# p02.net
KiCad netlist of a schematic drawn in EAGLE
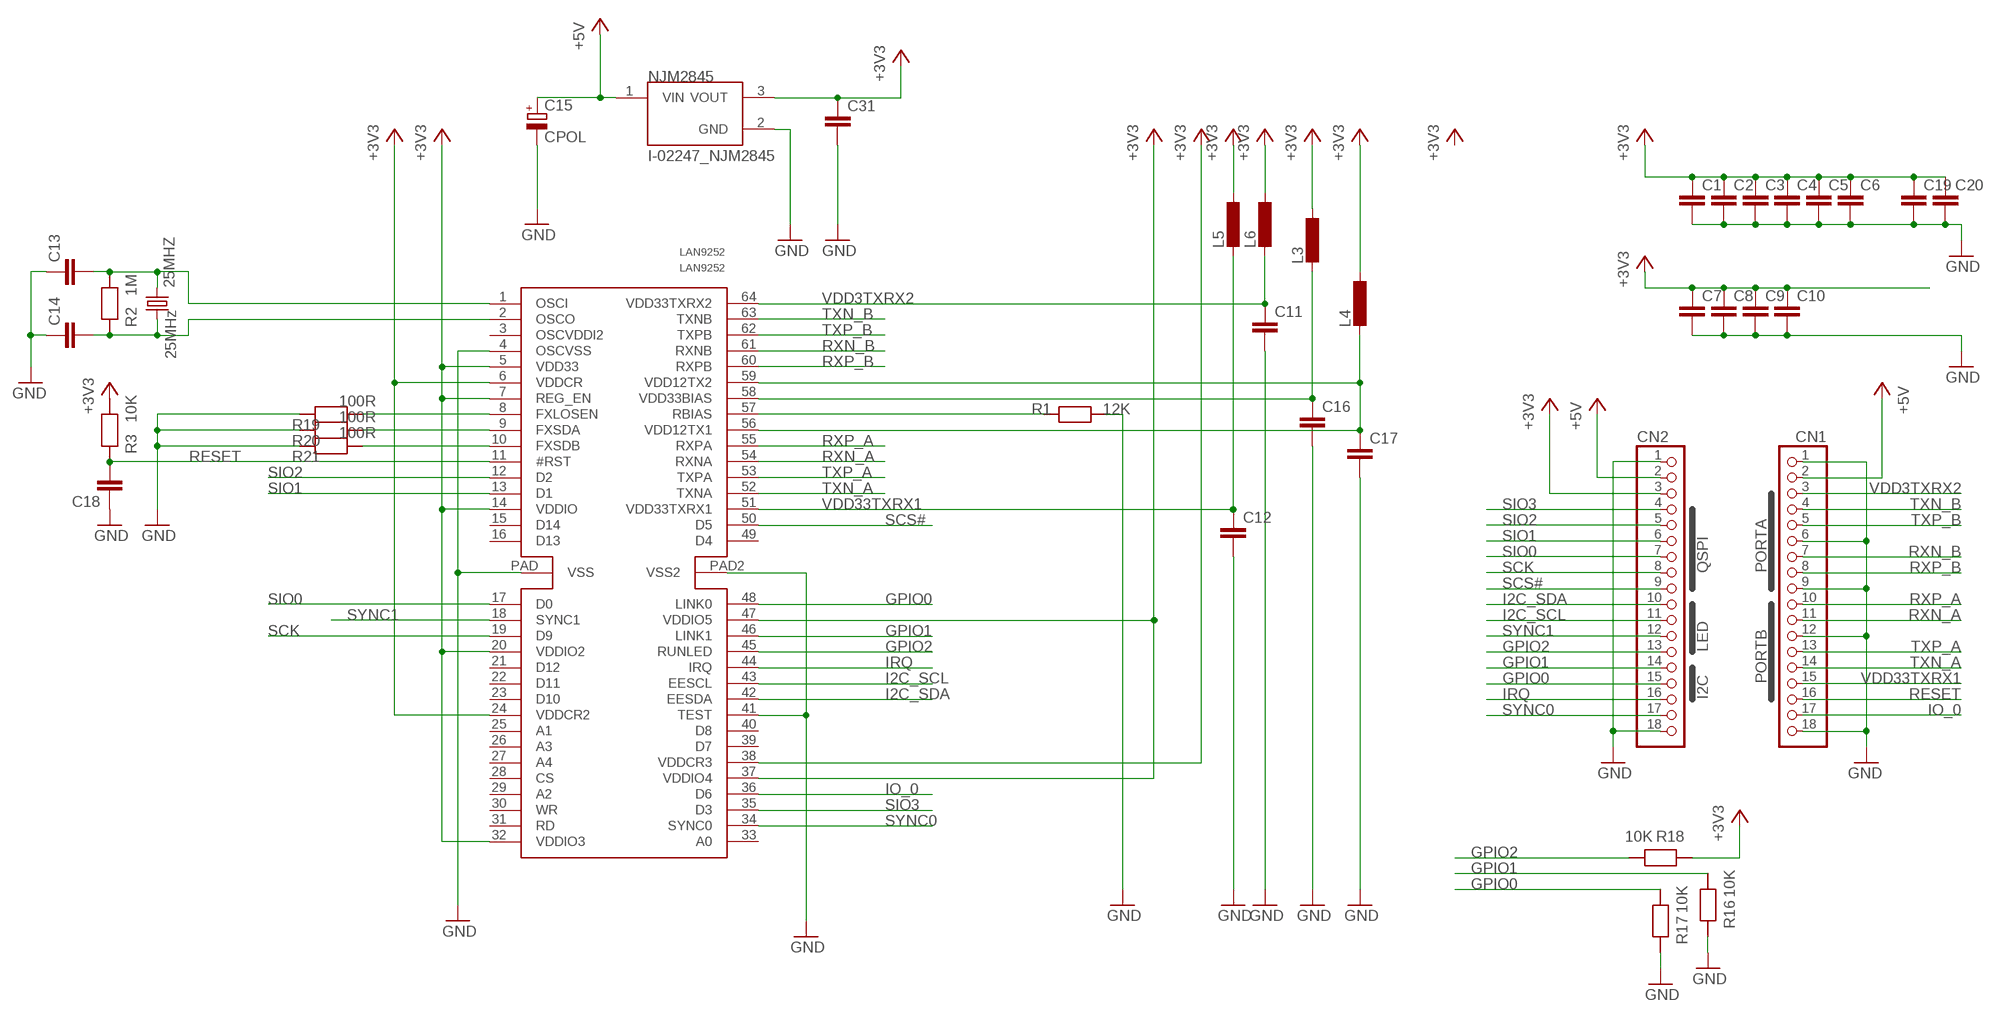
[diagram p0: schematic, sheet 1]

(export (version "E")
  (design (tool "Eeschema 10.0.6"))
  (components
    (comp (ref "25MHZ")
      (value "25MHz")
      (footprint "eagle-import:HC49_S")
      (libsource (lib "eagle-import") (part "CRYSTALHC49S"))
    )
    (comp (ref "C1")
      (value "C_1068")
      (footprint "eagle-import:C0603")
      (libsource (lib "eagle-import") (part "C_1068"))
    )
    (comp (ref "C2")
      (value "C_1068")
      (footprint "eagle-import:C0603")
      (libsource (lib "eagle-import") (part "C_1068"))
    )
    (comp (ref "C3")
      (value "C_1068")
      (footprint "eagle-import:C0603")
      (libsource (lib "eagle-import") (part "C_1068"))
    )
    (comp (ref "C4")
      (value "C_1068")
      (footprint "eagle-import:C0603")
      (libsource (lib "eagle-import") (part "C_1068"))
    )
    (comp (ref "C5")
      (value "C_1068")
      (footprint "eagle-import:C0603")
      (libsource (lib "eagle-import") (part "C_1068"))
    )
    (comp (ref "C6")
      (value "C_1068")
      (footprint "eagle-import:C0603")
      (libsource (lib "eagle-import") (part "C_1068"))
    )
    (comp (ref "C7")
      (value "C_1068")
      (footprint "eagle-import:C0603")
      (libsource (lib "eagle-import") (part "C_1068"))
    )
    (comp (ref "C8")
      (value "C_1068")
      (footprint "eagle-import:C0603")
      (libsource (lib "eagle-import") (part "C_1068"))
    )
    (comp (ref "C9")
      (value "C_1068")
      (footprint "eagle-import:C0603")
      (libsource (lib "eagle-import") (part "C_1068"))
    )
    (comp (ref "C10")
      (value "C_1068")
      (footprint "eagle-import:C0603")
      (libsource (lib "eagle-import") (part "C_1068"))
    )
    (comp (ref "C11")
      (value "C_1068")
      (footprint "eagle-import:C0603")
      (libsource (lib "eagle-import") (part "C_1068"))
    )
    (comp (ref "C12")
      (value "C_1068")
      (footprint "eagle-import:C0603")
      (libsource (lib "eagle-import") (part "C_1068"))
    )
    (comp (ref "C13")
      (value "C_1068")
      (footprint "eagle-import:C0603")
      (libsource (lib "eagle-import") (part "C_1068"))
    )
    (comp (ref "C14")
      (value "C_1068")
      (footprint "eagle-import:C0603")
      (libsource (lib "eagle-import") (part "C_1068"))
    )
    (comp (ref "C15")
      (value "CPOL")
      (footprint "eagle-import:153CLV-0605")
      (libsource (lib "eagle-import") (part "CPOL"))
    )
    (comp (ref "C16")
      (value "C_1068")
      (footprint "eagle-import:C0603")
      (libsource (lib "eagle-import") (part "C_1068"))
    )
    (comp (ref "C17")
      (value "C_1068")
      (footprint "eagle-import:C0603")
      (libsource (lib "eagle-import") (part "C_1068"))
    )
    (comp (ref "C18")
      (value "C_1068")
      (footprint "eagle-import:C0603")
      (libsource (lib "eagle-import") (part "C_1068"))
    )
    (comp (ref "C19")
      (value "C_2012")
      (footprint "eagle-import:C0805K")
      (libsource (lib "eagle-import") (part "C_2012"))
    )
    (comp (ref "C20")
      (value "C_2012")
      (footprint "eagle-import:C0805K")
      (libsource (lib "eagle-import") (part "C_2012"))
    )
    (comp (ref "C31")
      (value "C_1068")
      (footprint "eagle-import:C0603")
      (libsource (lib "eagle-import") (part "C_1068"))
    )
    (comp (ref "CN1")
      (value "PINHD-1X18")
      (footprint "eagle-import:1X18")
      (libsource (lib "eagle-import") (part "PINHD-1X18"))
    )
    (comp (ref "CN2")
      (value "PINHD-1X18")
      (footprint "eagle-import:1X18")
      (libsource (lib "eagle-import") (part "PINHD-1X18"))
    )
    (comp (ref "L3")
      (value "L-EUL2012C")
      (footprint "eagle-import:L2012C")
      (libsource (lib "eagle-import") (part "L-EUL2012C"))
    )
    (comp (ref "L4")
      (value "L-EUL2012C")
      (footprint "eagle-import:L2012C")
      (libsource (lib "eagle-import") (part "L-EUL2012C"))
    )
    (comp (ref "L5")
      (value "L-EUL2012C")
      (footprint "eagle-import:L2012C")
      (libsource (lib "eagle-import") (part "L-EUL2012C"))
    )
    (comp (ref "L6")
      (value "L-EUL2012C")
      (footprint "eagle-import:L2012C")
      (libsource (lib "eagle-import") (part "L-EUL2012C"))
    )
    (comp (ref "LAN9252")
      (value "LAN9252")
      (footprint "eagle-import:QFN-64_02")
      (libsource (lib "eagle-import") (part "LAN9252"))
    )
    (comp (ref "NJM2845")
      (value "I-02247_NJM2845")
      (footprint "eagle-import:TO252")
      (libsource (lib "eagle-import") (part "I-02247_NJM2845"))
    )
    (comp (ref "R1")
      (value "12K")
      (footprint "eagle-import:R0603")
      (libsource (lib "eagle-import") (part "R_1068"))
    )
    (comp (ref "R2")
      (value "1M")
      (footprint "eagle-import:R0603")
      (libsource (lib "eagle-import") (part "R_1068"))
    )
    (comp (ref "R3")
      (value "10K")
      (footprint "eagle-import:R0603")
      (libsource (lib "eagle-import") (part "R_1068"))
    )
    (comp (ref "R16")
      (value "10K")
      (footprint "eagle-import:R0603")
      (libsource (lib "eagle-import") (part "R_1068"))
    )
    (comp (ref "R17")
      (value "10K")
      (footprint "eagle-import:R0603")
      (libsource (lib "eagle-import") (part "R_1068"))
    )
    (comp (ref "R18")
      (value "10K")
      (footprint "eagle-import:R0603")
      (libsource (lib "eagle-import") (part "R_1068"))
    )
    (comp (ref "R19")
      (value "100R")
      (footprint "eagle-import:R0603")
      (libsource (lib "eagle-import") (part "R_1068"))
    )
    (comp (ref "R20")
      (value "100R")
      (footprint "eagle-import:R0603")
      (libsource (lib "eagle-import") (part "R_1068"))
    )
    (comp (ref "R21")
      (value "100R")
      (footprint "eagle-import:R0603")
      (libsource (lib "eagle-import") (part "R_1068"))
    )
  )
  (nets
    (net (code "1") (name "+3V3") (class "Default")
      (node (ref "C1") (pin "1") (pinfunction "1_1") (pintype "passive"))
      (node (ref "C10") (pin "1") (pinfunction "1_1") (pintype "passive"))
      (node (ref "C19") (pin "1") (pinfunction "1_1") (pintype "passive"))
      (node (ref "C2") (pin "1") (pinfunction "1_1") (pintype "passive"))
      (node (ref "C20") (pin "1") (pinfunction "1_1") (pintype "passive"))
      (node (ref "C3") (pin "1") (pinfunction "1_1") (pintype "passive"))
      (node (ref "C31") (pin "1") (pinfunction "1_1") (pintype "passive"))
      (node (ref "C4") (pin "1") (pinfunction "1_1") (pintype "passive"))
      (node (ref "C5") (pin "1") (pinfunction "1_1") (pintype "passive"))
      (node (ref "C6") (pin "1") (pinfunction "1_1") (pintype "passive"))
      (node (ref "C7") (pin "1") (pinfunction "1_1") (pintype "passive"))
      (node (ref "C8") (pin "1") (pinfunction "1_1") (pintype "passive"))
      (node (ref "C9") (pin "1") (pinfunction "1_1") (pintype "passive"))
      (node (ref "CN2") (pin "3") (pinfunction "3_3") (pintype "passive"))
      (node (ref "L3") (pin "1") (pinfunction "1_1") (pintype "passive"))
      (node (ref "L4") (pin "1") (pinfunction "1_1") (pintype "passive"))
      (node (ref "L5") (pin "1") (pinfunction "1_1") (pintype "passive"))
      (node (ref "L6") (pin "1") (pinfunction "1_1") (pintype "passive"))
      (node (ref "LAN9252") (pin "14") (pinfunction "VDDIO_14") (pintype "bidirectional"))
      (node (ref "LAN9252") (pin "20") (pinfunction "VDDIO2_20") (pintype "bidirectional"))
      (node (ref "LAN9252") (pin "24") (pinfunction "VDDCR2_24") (pintype "bidirectional"))
      (node (ref "LAN9252") (pin "32") (pinfunction "VDDIO3_32") (pintype "bidirectional"))
      (node (ref "LAN9252") (pin "37") (pinfunction "VDDIO4_37") (pintype "bidirectional"))
      (node (ref "LAN9252") (pin "38") (pinfunction "VDDCR3_38") (pintype "bidirectional"))
      (node (ref "LAN9252") (pin "47") (pinfunction "VDDIO5_47") (pintype "bidirectional"))
      (node (ref "LAN9252") (pin "5") (pinfunction "VDD33_5") (pintype "bidirectional"))
      (node (ref "LAN9252") (pin "6") (pinfunction "VDDCR_6") (pintype "bidirectional"))
      (node (ref "LAN9252") (pin "7") (pinfunction "REG_EN_7") (pintype "bidirectional"))
      (node (ref "NJM2845") (pin "3") (pinfunction "VOUT_3") (pintype "bidirectional"))
      (node (ref "R18") (pin "1") (pinfunction "1_1") (pintype "bidirectional"))
      (node (ref "R3") (pin "2") (pinfunction "2_2") (pintype "bidirectional"))
    )
    (net (code "2") (name "+5V") (class "Default")
      (node (ref "C15") (pin "+") (pinfunction "+_+") (pintype "passive"))
      (node (ref "CN1") (pin "2") (pinfunction "2_2") (pintype "passive"))
      (node (ref "CN2") (pin "2") (pinfunction "2_2") (pintype "passive"))
      (node (ref "NJM2845") (pin "1") (pinfunction "VIN_1") (pintype "bidirectional"))
    )
    (net (code "3") (name "/GPIO0") (class "Default")
      (node (ref "CN2") (pin "15") (pinfunction "15_15") (pintype "passive"))
      (node (ref "LAN9252") (pin "48") (pinfunction "LINK0_48") (pintype "bidirectional"))
      (node (ref "R17") (pin "2") (pinfunction "2_2") (pintype "bidirectional"))
    )
    (net (code "4") (name "/GPIO1") (class "Default")
      (node (ref "CN2") (pin "14") (pinfunction "14_14") (pintype "passive"))
      (node (ref "LAN9252") (pin "46") (pinfunction "LINK1_46") (pintype "bidirectional"))
      (node (ref "R16") (pin "2") (pinfunction "2_2") (pintype "bidirectional"))
    )
    (net (code "5") (name "/GPIO2") (class "Default")
      (node (ref "CN2") (pin "13") (pinfunction "13_13") (pintype "passive"))
      (node (ref "LAN9252") (pin "45") (pinfunction "RUNLED_45") (pintype "bidirectional"))
      (node (ref "R18") (pin "2") (pinfunction "2_2") (pintype "bidirectional"))
    )
    (net (code "6") (name "/I2C_SCL") (class "Default")
      (node (ref "CN2") (pin "11") (pinfunction "11_11") (pintype "passive"))
      (node (ref "LAN9252") (pin "43") (pinfunction "EESCL_43") (pintype "bidirectional"))
    )
    (net (code "7") (name "/I2C_SDA") (class "Default")
      (node (ref "CN2") (pin "10") (pinfunction "10_10") (pintype "passive"))
      (node (ref "LAN9252") (pin "42") (pinfunction "EESDA_42") (pintype "bidirectional"))
    )
    (net (code "8") (name "/IO_0") (class "Default")
      (node (ref "CN1") (pin "17") (pinfunction "17_17") (pintype "passive"))
      (node (ref "LAN9252") (pin "36") (pinfunction "D6_36") (pintype "bidirectional"))
    )
    (net (code "9") (name "/IRQ") (class "Default")
      (node (ref "CN2") (pin "16") (pinfunction "16_16") (pintype "passive"))
      (node (ref "LAN9252") (pin "44") (pinfunction "IRQ_44") (pintype "bidirectional"))
    )
    (net (code "10") (name "/RESET") (class "Default")
      (node (ref "C18") (pin "2") (pinfunction "2_2") (pintype "passive"))
      (node (ref "CN1") (pin "16") (pinfunction "16_16") (pintype "passive"))
      (node (ref "LAN9252") (pin "11") (pinfunction "#RST_11") (pintype "bidirectional"))
      (node (ref "R3") (pin "1") (pinfunction "1_1") (pintype "bidirectional"))
    )
    (net (code "11") (name "/RXN_A") (class "Default")
      (node (ref "CN1") (pin "11") (pinfunction "11_11") (pintype "passive"))
      (node (ref "LAN9252") (pin "54") (pinfunction "RXNA_54") (pintype "bidirectional"))
    )
    (net (code "12") (name "/RXN_B") (class "Default")
      (node (ref "CN1") (pin "7") (pinfunction "7_7") (pintype "passive"))
      (node (ref "LAN9252") (pin "61") (pinfunction "RXNB_61") (pintype "bidirectional"))
    )
    (net (code "13") (name "/RXP_A") (class "Default")
      (node (ref "CN1") (pin "10") (pinfunction "10_10") (pintype "passive"))
      (node (ref "LAN9252") (pin "55") (pinfunction "RXPA_55") (pintype "bidirectional"))
    )
    (net (code "14") (name "/RXP_B") (class "Default")
      (node (ref "CN1") (pin "8") (pinfunction "8_8") (pintype "passive"))
      (node (ref "LAN9252") (pin "60") (pinfunction "RXPB_60") (pintype "bidirectional"))
    )
    (net (code "15") (name "/SCK") (class "Default")
      (node (ref "CN2") (pin "8") (pinfunction "8_8") (pintype "passive"))
      (node (ref "LAN9252") (pin "19") (pinfunction "D9_19") (pintype "bidirectional"))
    )
    (net (code "16") (name "/SCS#") (class "Default")
      (node (ref "CN2") (pin "9") (pinfunction "9_9") (pintype "passive"))
      (node (ref "LAN9252") (pin "50") (pinfunction "D5_50") (pintype "bidirectional"))
    )
    (net (code "17") (name "/SIO0") (class "Default")
      (node (ref "CN2") (pin "7") (pinfunction "7_7") (pintype "passive"))
      (node (ref "LAN9252") (pin "17") (pinfunction "D0_17") (pintype "bidirectional"))
    )
    (net (code "18") (name "/SIO1") (class "Default")
      (node (ref "CN2") (pin "6") (pinfunction "6_6") (pintype "passive"))
      (node (ref "LAN9252") (pin "13") (pinfunction "D1_13") (pintype "bidirectional"))
    )
    (net (code "19") (name "/SIO2") (class "Default")
      (node (ref "CN2") (pin "5") (pinfunction "5_5") (pintype "passive"))
      (node (ref "LAN9252") (pin "12") (pinfunction "D2_12") (pintype "bidirectional"))
    )
    (net (code "20") (name "/SIO3") (class "Default")
      (node (ref "CN2") (pin "4") (pinfunction "4_4") (pintype "passive"))
      (node (ref "LAN9252") (pin "35") (pinfunction "D3_35") (pintype "bidirectional"))
    )
    (net (code "21") (name "/SYNC0") (class "Default")
      (node (ref "CN2") (pin "17") (pinfunction "17_17") (pintype "passive"))
      (node (ref "LAN9252") (pin "34") (pinfunction "SYNC0_34") (pintype "bidirectional"))
    )
    (net (code "22") (name "/SYNC1") (class "Default")
      (node (ref "CN2") (pin "12") (pinfunction "12_12") (pintype "passive"))
      (node (ref "LAN9252") (pin "18") (pinfunction "SYNC1_18") (pintype "bidirectional"))
    )
    (net (code "23") (name "/TXN_A") (class "Default")
      (node (ref "CN1") (pin "14") (pinfunction "14_14") (pintype "passive"))
      (node (ref "LAN9252") (pin "52") (pinfunction "TXNA_52") (pintype "bidirectional"))
    )
    (net (code "24") (name "/TXN_B") (class "Default")
      (node (ref "CN1") (pin "4") (pinfunction "4_4") (pintype "passive"))
      (node (ref "LAN9252") (pin "63") (pinfunction "TXNB_63") (pintype "bidirectional"))
    )
    (net (code "25") (name "/TXP_A") (class "Default")
      (node (ref "CN1") (pin "13") (pinfunction "13_13") (pintype "passive"))
      (node (ref "LAN9252") (pin "53") (pinfunction "TXPA_53") (pintype "bidirectional"))
    )
    (net (code "26") (name "/TXP_B") (class "Default")
      (node (ref "CN1") (pin "5") (pinfunction "5_5") (pintype "passive"))
      (node (ref "LAN9252") (pin "62") (pinfunction "TXPB_62") (pintype "bidirectional"))
    )
    (net (code "27") (name "/VDD3TXRX2") (class "Default")
      (node (ref "C11") (pin "1") (pinfunction "1_1") (pintype "passive"))
      (node (ref "CN1") (pin "3") (pinfunction "3_3") (pintype "passive"))
      (node (ref "L6") (pin "2") (pinfunction "2_2") (pintype "passive"))
      (node (ref "LAN9252") (pin "64") (pinfunction "VDD33TXRX2_64") (pintype "bidirectional"))
    )
    (net (code "28") (name "/VDD33TXRX1") (class "Default")
      (node (ref "C12") (pin "1") (pinfunction "1_1") (pintype "passive"))
      (node (ref "CN1") (pin "15") (pinfunction "15_15") (pintype "passive"))
      (node (ref "L5") (pin "2") (pinfunction "2_2") (pintype "passive"))
      (node (ref "LAN9252") (pin "51") (pinfunction "VDD33TXRX1_51") (pintype "bidirectional"))
    )
    (net (code "29") (name "GND") (class "Default")
      (node (ref "C1") (pin "2") (pinfunction "2_2") (pintype "passive"))
      (node (ref "C10") (pin "2") (pinfunction "2_2") (pintype "passive"))
      (node (ref "C11") (pin "2") (pinfunction "2_2") (pintype "passive"))
      (node (ref "C12") (pin "2") (pinfunction "2_2") (pintype "passive"))
      (node (ref "C13") (pin "1") (pinfunction "1_1") (pintype "passive"))
      (node (ref "C14") (pin "1") (pinfunction "1_1") (pintype "passive"))
      (node (ref "C15") (pin "-") (pinfunction "-_-") (pintype "passive"))
      (node (ref "C16") (pin "2") (pinfunction "2_2") (pintype "passive"))
      (node (ref "C17") (pin "2") (pinfunction "2_2") (pintype "passive"))
      (node (ref "C18") (pin "1") (pinfunction "1_1") (pintype "passive"))
      (node (ref "C19") (pin "2") (pinfunction "2_2") (pintype "passive"))
      (node (ref "C2") (pin "2") (pinfunction "2_2") (pintype "passive"))
      (node (ref "C20") (pin "2") (pinfunction "2_2") (pintype "passive"))
      (node (ref "C3") (pin "2") (pinfunction "2_2") (pintype "passive"))
      (node (ref "C31") (pin "2") (pinfunction "2_2") (pintype "passive"))
      (node (ref "C4") (pin "2") (pinfunction "2_2") (pintype "passive"))
      (node (ref "C5") (pin "2") (pinfunction "2_2") (pintype "passive"))
      (node (ref "C6") (pin "2") (pinfunction "2_2") (pintype "passive"))
      (node (ref "C7") (pin "2") (pinfunction "2_2") (pintype "passive"))
      (node (ref "C8") (pin "2") (pinfunction "2_2") (pintype "passive"))
      (node (ref "C9") (pin "2") (pinfunction "2_2") (pintype "passive"))
      (node (ref "CN1") (pin "1") (pinfunction "1_1") (pintype "passive"))
      (node (ref "CN1") (pin "12") (pinfunction "12_12") (pintype "passive"))
      (node (ref "CN1") (pin "18") (pinfunction "18_18") (pintype "passive"))
      (node (ref "CN1") (pin "6") (pinfunction "6_6") (pintype "passive"))
      (node (ref "CN1") (pin "9") (pinfunction "9_9") (pintype "passive"))
      (node (ref "CN2") (pin "1") (pinfunction "1_1") (pintype "passive"))
      (node (ref "CN2") (pin "18") (pinfunction "18_18") (pintype "passive"))
      (node (ref "LAN9252") (pin "4") (pinfunction "OSCVSS_4") (pintype "bidirectional"))
      (node (ref "LAN9252") (pin "41") (pinfunction "TEST_41") (pintype "bidirectional"))
      (node (ref "LAN9252") (pin "PAD") (pinfunction "VSS_PAD") (pintype "bidirectional"))
      (node (ref "LAN9252") (pin "PAD2") (pinfunction "VSS2_PAD2") (pintype "bidirectional"))
      (node (ref "NJM2845") (pin "2") (pinfunction "GND_2") (pintype "bidirectional"))
      (node (ref "R1") (pin "1") (pinfunction "1_1") (pintype "bidirectional"))
      (node (ref "R16") (pin "1") (pinfunction "1_1") (pintype "bidirectional"))
      (node (ref "R17") (pin "1") (pinfunction "1_1") (pintype "bidirectional"))
      (node (ref "R19") (pin "1") (pinfunction "1_1") (pintype "bidirectional"))
      (node (ref "R20") (pin "1") (pinfunction "1_1") (pintype "bidirectional"))
      (node (ref "R21") (pin "1") (pinfunction "1_1") (pintype "bidirectional"))
    )
    (net (code "30") (name "Net-(LAN9252-FXLOSEN)") (class "Default")
      (node (ref "LAN9252") (pin "8") (pinfunction "FXLOSEN_8") (pintype "bidirectional"))
      (node (ref "R19") (pin "2") (pinfunction "2_2") (pintype "bidirectional"))
    )
    (net (code "31") (name "Net-(LAN9252-FXSDA)") (class "Default")
      (node (ref "LAN9252") (pin "9") (pinfunction "FXSDA_9") (pintype "bidirectional"))
      (node (ref "R20") (pin "2") (pinfunction "2_2") (pintype "bidirectional"))
    )
    (net (code "32") (name "Net-(LAN9252-FXSDB)") (class "Default")
      (node (ref "LAN9252") (pin "10") (pinfunction "FXSDB_10") (pintype "bidirectional"))
      (node (ref "R21") (pin "2") (pinfunction "2_2") (pintype "bidirectional"))
    )
    (net (code "33") (name "Net-(LAN9252-OSCI)") (class "Default")
      (node (ref "25MHZ") (pin "2") (pinfunction "2_2") (pintype "passive"))
      (node (ref "C13") (pin "2") (pinfunction "2_2") (pintype "passive"))
      (node (ref "LAN9252") (pin "1") (pinfunction "OSCI_1") (pintype "bidirectional"))
      (node (ref "R2") (pin "2") (pinfunction "2_2") (pintype "bidirectional"))
    )
    (net (code "34") (name "Net-(LAN9252-OSCO)") (class "Default")
      (node (ref "25MHZ") (pin "1") (pinfunction "1_1") (pintype "passive"))
      (node (ref "C14") (pin "2") (pinfunction "2_2") (pintype "passive"))
      (node (ref "LAN9252") (pin "2") (pinfunction "OSCO_2") (pintype "bidirectional"))
      (node (ref "R2") (pin "1") (pinfunction "1_1") (pintype "bidirectional"))
    )
    (net (code "35") (name "Net-(LAN9252-RBIAS)") (class "Default")
      (node (ref "LAN9252") (pin "57") (pinfunction "RBIAS_57") (pintype "bidirectional"))
      (node (ref "R1") (pin "2") (pinfunction "2_2") (pintype "bidirectional"))
    )
    (net (code "36") (name "Net-(LAN9252-VDD12TX1)") (class "Default")
      (node (ref "C17") (pin "1") (pinfunction "1_1") (pintype "passive"))
      (node (ref "L4") (pin "2") (pinfunction "2_2") (pintype "passive"))
      (node (ref "LAN9252") (pin "56") (pinfunction "VDD12TX1_56") (pintype "bidirectional"))
      (node (ref "LAN9252") (pin "59") (pinfunction "VDD12TX2_59") (pintype "bidirectional"))
    )
    (net (code "37") (name "Net-(LAN9252-VDD33BIAS)") (class "Default")
      (node (ref "C16") (pin "1") (pinfunction "1_1") (pintype "passive"))
      (node (ref "L3") (pin "2") (pinfunction "2_2") (pintype "passive"))
      (node (ref "LAN9252") (pin "58") (pinfunction "VDD33BIAS_58") (pintype "bidirectional"))
    )
    (net (code "38") (name "unconnected-(LAN9252-A0-Pad33)") (class "Default")
      (node (ref "LAN9252") (pin "33") (pinfunction "A0_33") (pintype "bidirectional"))
    )
    (net (code "39") (name "unconnected-(LAN9252-A1-Pad25)") (class "Default")
      (node (ref "LAN9252") (pin "25") (pinfunction "A1_25") (pintype "bidirectional"))
    )
    (net (code "40") (name "unconnected-(LAN9252-A2-Pad29)") (class "Default")
      (node (ref "LAN9252") (pin "29") (pinfunction "A2_29") (pintype "bidirectional"))
    )
    (net (code "41") (name "unconnected-(LAN9252-A3-Pad26)") (class "Default")
      (node (ref "LAN9252") (pin "26") (pinfunction "A3_26") (pintype "bidirectional"))
    )
    (net (code "42") (name "unconnected-(LAN9252-A4-Pad27)") (class "Default")
      (node (ref "LAN9252") (pin "27") (pinfunction "A4_27") (pintype "bidirectional"))
    )
    (net (code "43") (name "unconnected-(LAN9252-CS-Pad28)") (class "Default")
      (node (ref "LAN9252") (pin "28") (pinfunction "CS_28") (pintype "bidirectional"))
    )
    (net (code "44") (name "unconnected-(LAN9252-D4-Pad49)") (class "Default")
      (node (ref "LAN9252") (pin "49") (pinfunction "D4_49") (pintype "bidirectional"))
    )
    (net (code "45") (name "unconnected-(LAN9252-D7-Pad39)") (class "Default")
      (node (ref "LAN9252") (pin "39") (pinfunction "D7_39") (pintype "bidirectional"))
    )
    (net (code "46") (name "unconnected-(LAN9252-D8-Pad40)") (class "Default")
      (node (ref "LAN9252") (pin "40") (pinfunction "D8_40") (pintype "bidirectional"))
    )
    (net (code "47") (name "unconnected-(LAN9252-D10-Pad23)") (class "Default")
      (node (ref "LAN9252") (pin "23") (pinfunction "D10_23") (pintype "bidirectional"))
    )
    (net (code "48") (name "unconnected-(LAN9252-D11-Pad22)") (class "Default")
      (node (ref "LAN9252") (pin "22") (pinfunction "D11_22") (pintype "bidirectional"))
    )
    (net (code "49") (name "unconnected-(LAN9252-D12-Pad21)") (class "Default")
      (node (ref "LAN9252") (pin "21") (pinfunction "D12_21") (pintype "bidirectional"))
    )
    (net (code "50") (name "unconnected-(LAN9252-D13-Pad16)") (class "Default")
      (node (ref "LAN9252") (pin "16") (pinfunction "D13_16") (pintype "bidirectional"))
    )
    (net (code "51") (name "unconnected-(LAN9252-D14-Pad15)") (class "Default")
      (node (ref "LAN9252") (pin "15") (pinfunction "D14_15") (pintype "bidirectional"))
    )
    (net (code "52") (name "unconnected-(LAN9252-OSCVDDI2-Pad3)") (class "Default")
      (node (ref "LAN9252") (pin "3") (pinfunction "OSCVDDI2_3") (pintype "bidirectional"))
    )
    (net (code "53") (name "unconnected-(LAN9252-RD-Pad31)") (class "Default")
      (node (ref "LAN9252") (pin "31") (pinfunction "RD_31") (pintype "bidirectional"))
    )
    (net (code "54") (name "unconnected-(LAN9252-WR-Pad30)") (class "Default")
      (node (ref "LAN9252") (pin "30") (pinfunction "WR_30") (pintype "bidirectional"))
    )
  )
)
